# IMX8_eMMC.net
KiCad netlist of a schematic drawn in Altium Designer
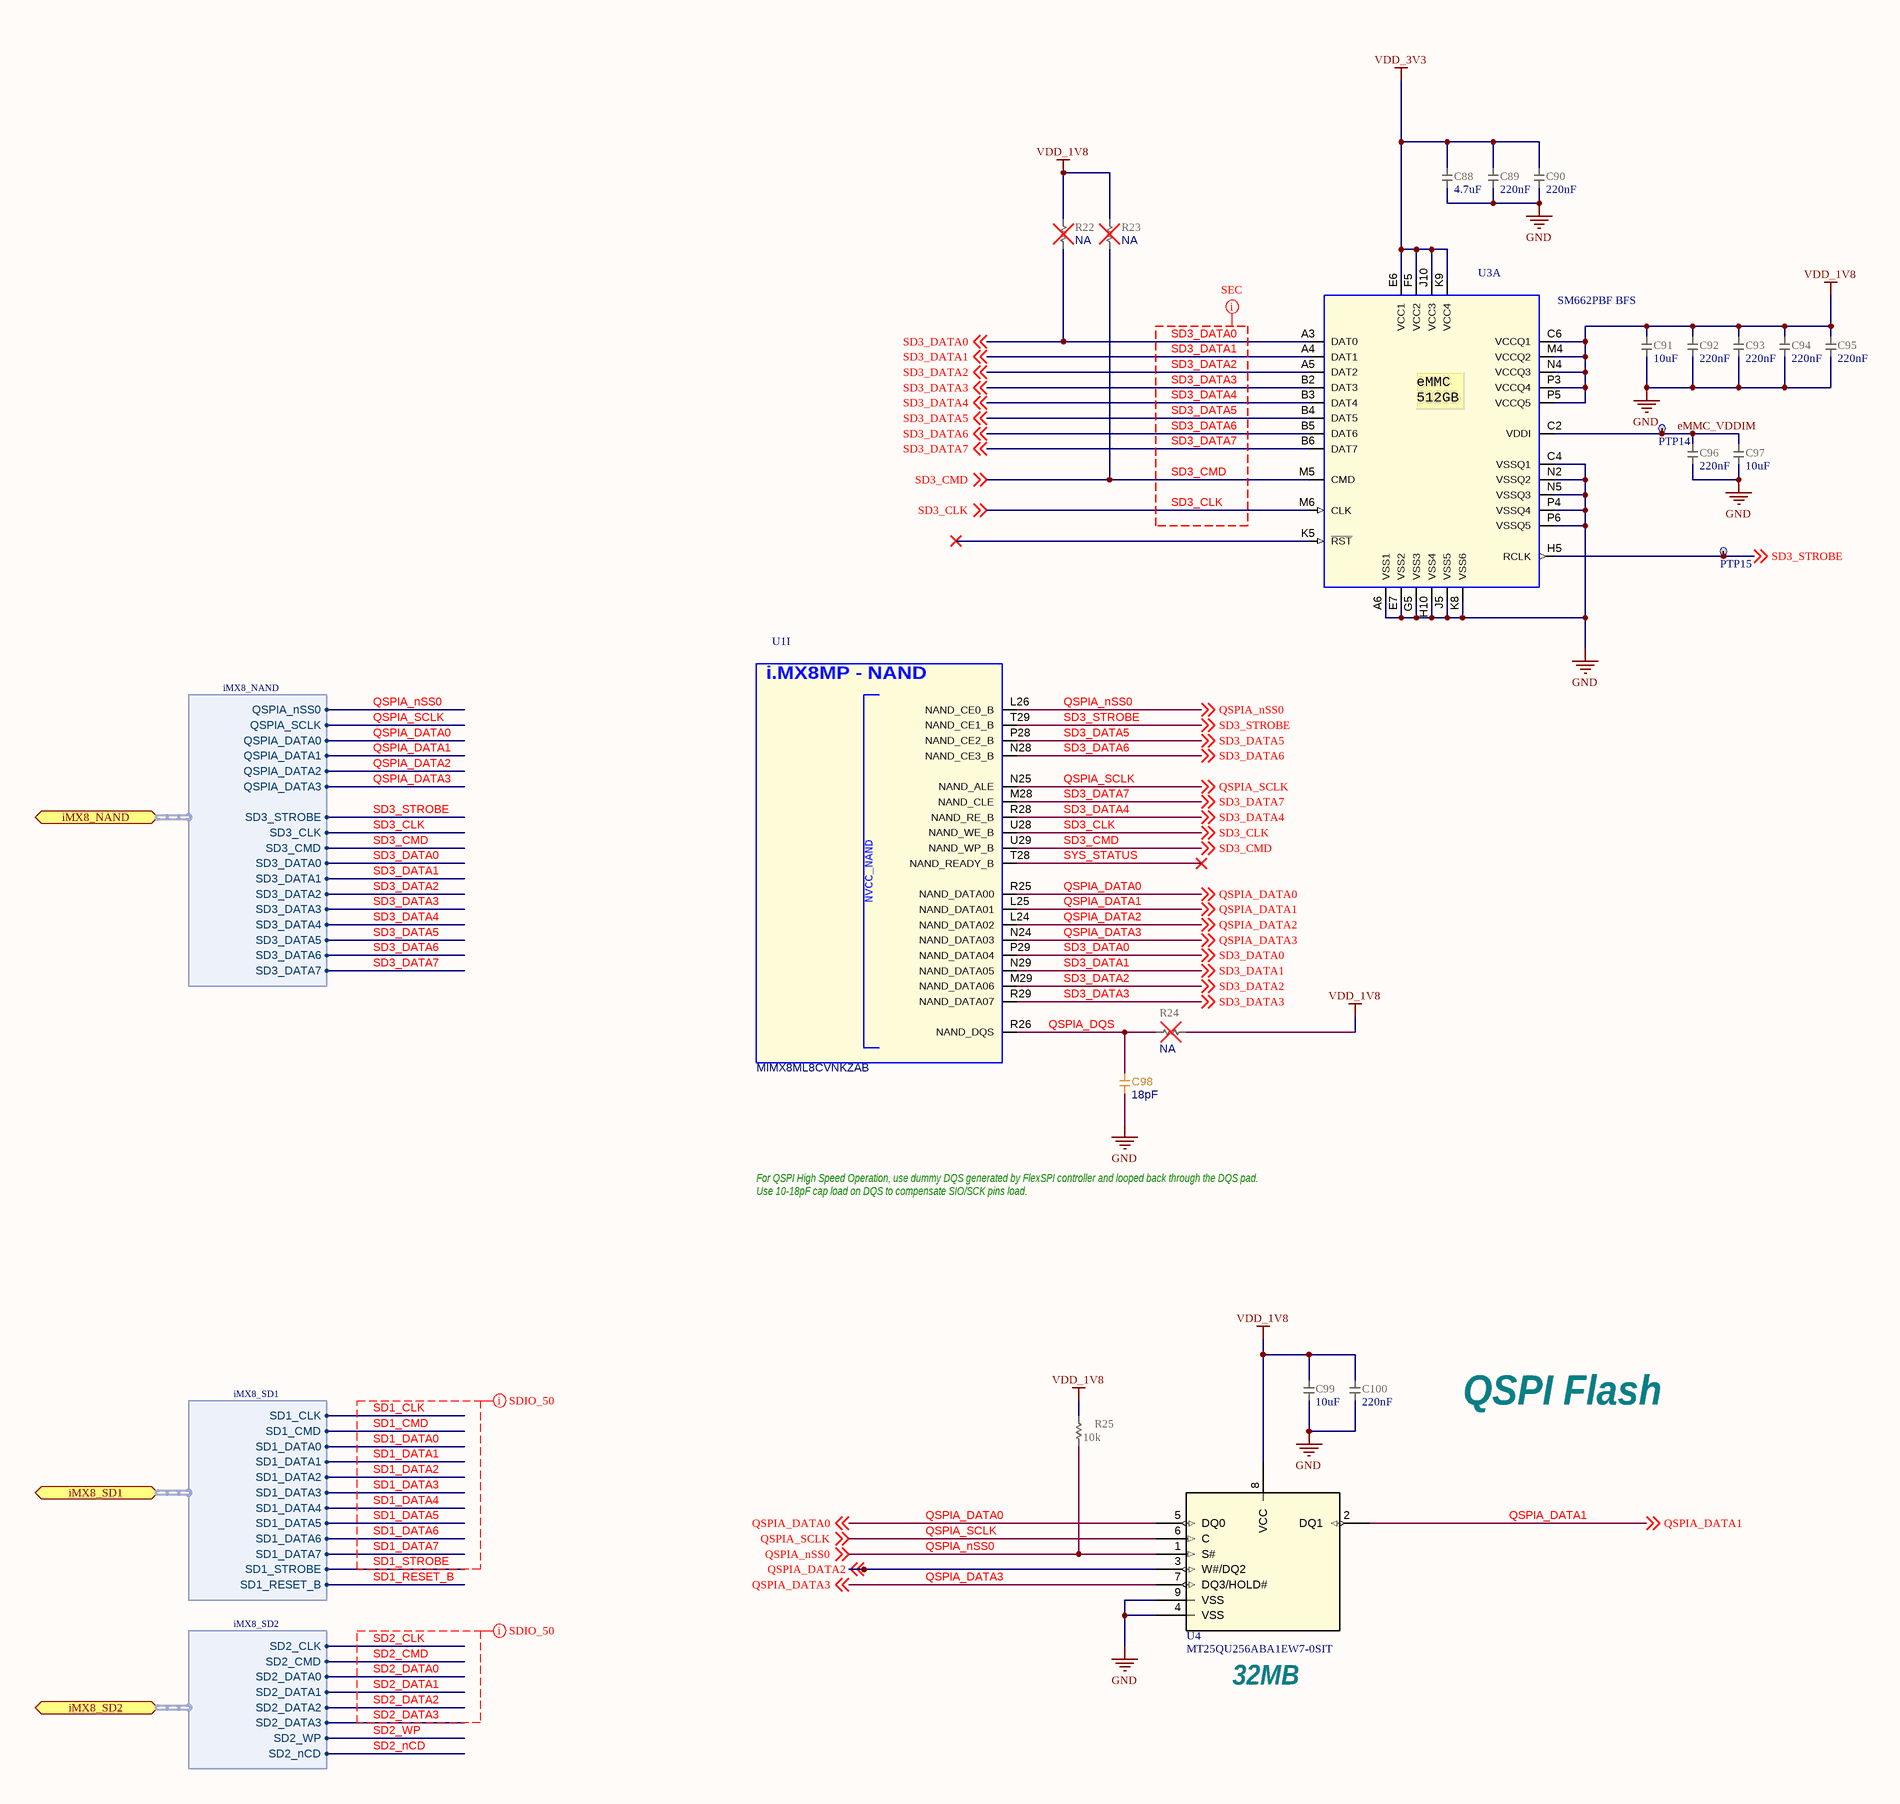
[diagram p0: IMX8_eMMC.SchDoc, left]
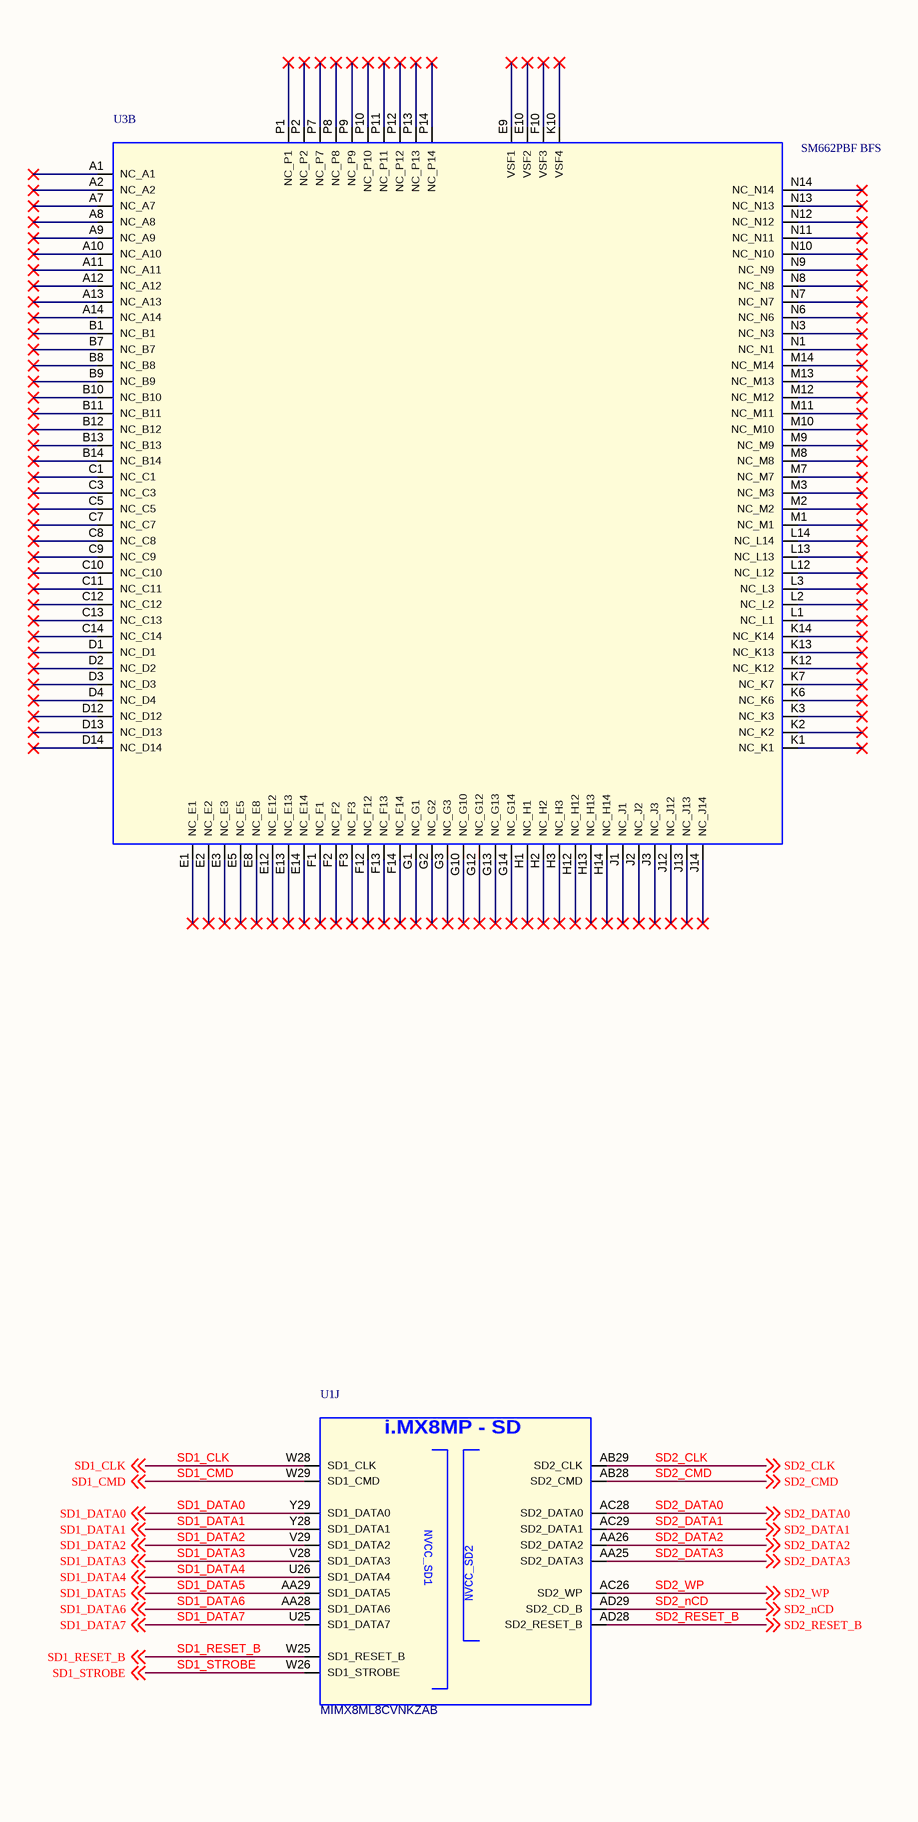
[diagram p1: IMX8_eMMC.SchDoc, right]

(export (version "E")
  (design (tool "Eeschema 10.0.6"))
  (components
    (comp (ref "C88")
      (value "4.7uF")
      (footprint "CAP_0402_H09W07_UN1Q")
      (description "CAP")
      (fields (field (name "PART NUMBER") "GRT155C81A475ME13J") (field (name "MANUFACTURER") "Murata"))
      (libsource (lib "robo_cam") (part "CMP-001-000888-12"))
    )
    (comp (ref "C89")
      (value "220nF")
      (footprint "CAP_0201_UN1Q")
      (description "CAP")
      (fields (field (name "PART NUMBER") "GRM033C81A224KE01D") (field (name "MANUFACTURER") "Murata"))
      (libsource (lib "robo_cam") (part "CMP-001-000889-11"))
    )
    (comp (ref "C90")
      (value "220nF")
      (footprint "CAP_0201_UN1Q")
      (description "CAP")
      (fields (field (name "PART NUMBER") "GRM033C81A224KE01D") (field (name "MANUFACTURER") "Murata"))
      (libsource (lib "robo_cam") (part "CMP-001-000889-11"))
    )
    (comp (ref "C91")
      (value "10uF")
      (footprint "CAP_0402_H09W07_UN1Q")
      (description "CAP")
      (fields (field (name "VOLTAGE") "6.3V") (field (name "TOLERANCE") "+/-20%"))
      (libsource (lib "robo_cam") (part "CMP-001-000883-14"))
    )
    (comp (ref "C92")
      (value "220nF")
      (footprint "CAP_0201_UN1Q")
      (description "CAP")
      (fields (field (name "PART NUMBER") "GRM033C81A224KE01D") (field (name "MANUFACTURER") "Murata"))
      (libsource (lib "robo_cam") (part "CMP-001-000889-11"))
    )
    (comp (ref "C93")
      (value "220nF")
      (footprint "CAP_0201_UN1Q")
      (description "CAP")
      (fields (field (name "PART NUMBER") "GRM033C81A224KE01D") (field (name "MANUFACTURER") "Murata"))
      (libsource (lib "robo_cam") (part "CMP-001-000889-11"))
    )
    (comp (ref "C94")
      (value "220nF")
      (footprint "CAP_0201_UN1Q")
      (description "CAP")
      (fields (field (name "PART NUMBER") "GRM033C81A224KE01D") (field (name "MANUFACTURER") "Murata"))
      (libsource (lib "robo_cam") (part "CMP-001-000889-11"))
    )
    (comp (ref "C95")
      (value "220nF")
      (footprint "CAP_0201_UN1Q")
      (description "CAP")
      (fields (field (name "PART NUMBER") "GRM033C81A224KE01D") (field (name "MANUFACTURER") "Murata"))
      (libsource (lib "robo_cam") (part "CMP-001-000889-11"))
    )
    (comp (ref "C96")
      (value "220nF")
      (footprint "CAP_0201_UN1Q")
      (description "CAP")
      (fields (field (name "PART NUMBER") "GRM033C81A224KE01D") (field (name "MANUFACTURER") "Murata"))
      (libsource (lib "robo_cam") (part "CMP-001-000889-11"))
    )
    (comp (ref "C97")
      (value "10uF")
      (footprint "CAP_0402_H09W07_UN1Q")
      (description "CAP")
      (fields (field (name "VOLTAGE") "6.3V") (field (name "TOLERANCE") "+/-20%"))
      (libsource (lib "robo_cam") (part "CMP-001-000883-14"))
    )
    (comp (ref "C98")
      (value "18pF")
      (footprint "CAP_0201_UN1Q")
      (description "CAP_RF_MATCHING")
      (fields (field (name "VOLTAGE") "25V") (field (name "TOLERANCE") "+/-2%"))
      (libsource (lib "robo_cam") (part "CMP-001-000400-12"))
    )
    (comp (ref "C99")
      (value "10uF")
      (footprint "CAP_0402_H09W07_UN1Q")
      (description "CAP")
      (fields (field (name "VOLTAGE") "6.3V") (field (name "TOLERANCE") "+/-20%"))
      (libsource (lib "robo_cam") (part "CMP-001-000883-14"))
    )
    (comp (ref "C100")
      (value "220nF")
      (footprint "CAP_0201_UN1Q")
      (description "CAP")
      (fields (field (name "PART NUMBER") "GRM033C81A224KE01D") (field (name "MANUFACTURER") "Murata"))
      (libsource (lib "robo_cam") (part "CMP-001-000889-11"))
    )
    (comp (ref "PTP14")
      (value "PTP_0.4mm")
      (footprint "PTP_0.4mm")
      (description "Production Testpoint 0.4mm. Flying probe. Use 1mm pitch.")
      (fields (field (name "PART NUMBER") "PTP 0.4mm"))
      (libsource (lib "robo_cam") (part "CMP-001-001296-3"))
    )
    (comp (ref "PTP15")
      (value "PTP_0.4mm")
      (footprint "PTP_0.4mm")
      (description "Production Testpoint 0.4mm. Flying probe. Use 1mm pitch.")
      (fields (field (name "PART NUMBER") "PTP 0.4mm"))
      (libsource (lib "robo_cam") (part "CMP-001-001296-3"))
    )
    (comp (ref "R22")
      (value "NA")
      (footprint "RES_0201_UN1Q")
      (description "Not Assembled - RES")
      (fields (field (name "Comment") "RES_0201_NA"))
      (libsource (lib "robo_cam") (part "CMP-001-000434-10"))
    )
    (comp (ref "R23")
      (value "NA")
      (footprint "RES_0201_UN1Q")
      (description "Not Assembled - RES")
      (fields (field (name "Comment") "RES_0201_NA"))
      (libsource (lib "robo_cam") (part "CMP-001-000434-10"))
    )
    (comp (ref "R24")
      (value "NA")
      (footprint "RES_0201_UN1Q")
      (description "Not Assembled - RES")
      (fields (field (name "Comment") "RES_0201_NA"))
      (libsource (lib "robo_cam") (part "CMP-001-000434-10"))
    )
    (comp (ref "R25")
      (value "10k")
      (footprint "RES_0201_UN1Q")
      (description "RES")
      (fields (field (name "TOLERANCE") "+/-1%"))
      (libsource (lib "RLC_UN1Q") (part "RES_0201_10k"))
    )
    (comp (ref "U1")
      (value "MIMX8ML8CVNKZAB")
      (footprint "BGA548C50P29X29_1500X1500X148")
      (description "CPU QUAD CORTEX A53+M4 1.6GHZ BGA548 Industrial")
      (fields
        (field (name "MANUFACTURER") "NXP Semiconductors")
        (field (name "PART NUMBER") "MIMX8ML8CVNKZAB")
        (field (name "SOURCE") "UUDET_KOMPONENTIT.SchLib")
      )
      (libsource (lib "robo_cam") (part "CMP-001-000983-8"))
    )
    (comp (ref "U3")
      (value "SM662PBF BFS")
      (footprint "GA153C50P14X14_1150X1300X120")
      (description "MEM NAND FLASH 512GB eMMC 5.1 HS400 2.7-3.6V, 1.8V VCCQ, TFBGA153 Ferri-eMMC Automotive")
      (fields
        (field (name "MANUFACTURER") "Silicon Motion")
        (field (name "PART NUMBER") "SM662PBF BFS")
        (field (name "MANUFACTURER PART NUMBER") "SM662PBFBFSS")
      )
      (libsource (lib "robo_cam") (part "CMP-001-001175-2"))
    )
    (comp (ref "U4")
      (value "MT25QU256ABA1EW7-0SIT")
      (footprint "W-PDFN-8MLP8_W7_MRN")
      (description "Description")
      (fields (field (name "COPYRIGHT") "Copyright (C) 2025 Ultra Librarian. All rights reserved."))
      (libsource (lib "MT25QU256ABA1EW7-0SIT") (part "MT25QU256ABA1EW7-0SIT"))
    )
  )
  (nets
    (net (code "4") (name "/QSPIA_DQS") (class "Default")
      (node (ref "C98") (pin "2") (pinfunction "2_2") (pintype "passive"))
      (node (ref "R24") (pin "1") (pinfunction "1_1") (pintype "passive"))
      (node (ref "U1") (pin "R26") (pinfunction "NAND_DQS_R26") (pintype "passive"))
    )
    (net (code "5") (name "/SYS_STATUS") (class "Default")
      (node (ref "U1") (pin "T28") (pinfunction "NAND_READY_B_T28") (pintype "passive+no_connect"))
    )
    (net (code "6") (name "/eMMC_VDDIM") (class "Default")
      (node (ref "C96") (pin "2") (pinfunction "2_2") (pintype "passive"))
      (node (ref "C97") (pin "1") (pinfunction "1_1") (pintype "passive"))
      (node (ref "PTP14") (pin "1") (pinfunction "TP_1") (pintype "passive"))
      (node (ref "U3") (pin "C2") (pinfunction "VDDI_C2") (pintype "power_in"))
    )
    (net (code "10") (name "GND") (class "Default")
      (node (ref "C100") (pin "2") (pinfunction "2_2") (pintype "passive"))
      (node (ref "C88") (pin "1") (pinfunction "1_1") (pintype "passive"))
      (node (ref "C89") (pin "1") (pinfunction "1_1") (pintype "passive"))
      (node (ref "C90") (pin "1") (pinfunction "1_1") (pintype "passive"))
      (node (ref "C91") (pin "2") (pinfunction "2_2") (pintype "passive"))
      (node (ref "C92") (pin "1") (pinfunction "1_1") (pintype "passive"))
      (node (ref "C93") (pin "1") (pinfunction "1_1") (pintype "passive"))
      (node (ref "C94") (pin "1") (pinfunction "1_1") (pintype "passive"))
      (node (ref "C95") (pin "1") (pinfunction "1_1") (pintype "passive"))
      (node (ref "C96") (pin "1") (pinfunction "1_1") (pintype "passive"))
      (node (ref "C97") (pin "2") (pinfunction "2_2") (pintype "passive"))
      (node (ref "C98") (pin "1") (pinfunction "1_1") (pintype "passive"))
      (node (ref "C99") (pin "2") (pinfunction "2_2") (pintype "passive"))
      (node (ref "U3") (pin "A6") (pinfunction "VSS1_A6") (pintype "power_in"))
      (node (ref "U3") (pin "C4") (pinfunction "VSSQ1_C4") (pintype "power_in"))
      (node (ref "U3") (pin "E7") (pinfunction "VSS2_E7") (pintype "power_in"))
      (node (ref "U3") (pin "G5") (pinfunction "VSS3_G5") (pintype "power_in"))
      (node (ref "U3") (pin "H10") (pinfunction "VSS4_H10") (pintype "power_in"))
      (node (ref "U3") (pin "J5") (pinfunction "VSS5_J5") (pintype "power_in"))
      (node (ref "U3") (pin "K8") (pinfunction "VSS6_K8") (pintype "power_in"))
      (node (ref "U3") (pin "N2") (pinfunction "VSSQ2_N2") (pintype "power_in"))
      (node (ref "U3") (pin "N5") (pinfunction "VSSQ3_N5") (pintype "power_in"))
      (node (ref "U3") (pin "P4") (pinfunction "VSSQ4_P4") (pintype "power_in"))
      (node (ref "U3") (pin "P6") (pinfunction "VSSQ5_P6") (pintype "power_in"))
      (node (ref "U4") (pin "4") (pinfunction "VSS_4") (pintype "power_in"))
      (node (ref "U4") (pin "9") (pinfunction "VSS_9") (pintype "power_in"))
    )
    (net (code "11") (name "QSPIA_DATA0") (class "Default")
      (node (ref "U1") (pin "R25") (pinfunction "NAND_DATA00_R25") (pintype "passive"))
      (node (ref "U4") (pin "5") (pinfunction "DQ0_5") (pintype "bidirectional"))
    )
    (net (code "12") (name "QSPIA_DATA1") (class "Default")
      (node (ref "U1") (pin "L25") (pinfunction "NAND_DATA01_L25") (pintype "passive"))
      (node (ref "U4") (pin "2") (pinfunction "DQ1_2") (pintype "bidirectional"))
    )
    (net (code "13") (name "QSPIA_DATA2") (class "Default")
      (node (ref "U1") (pin "L24") (pinfunction "NAND_DATA02_L24") (pintype "passive"))
      (node (ref "U4") (pin "3") (pinfunction "W#/DQ2_3") (pintype "bidirectional"))
    )
    (net (code "14") (name "QSPIA_DATA3") (class "Default")
      (node (ref "U1") (pin "N24") (pinfunction "NAND_DATA03_N24") (pintype "passive"))
      (node (ref "U4") (pin "7") (pinfunction "DQ3/HOLD#_7") (pintype "bidirectional"))
    )
    (net (code "15") (name "QSPIA_SCLK") (class "Default")
      (node (ref "U1") (pin "N25") (pinfunction "NAND_ALE_N25") (pintype "passive"))
      (node (ref "U4") (pin "6") (pinfunction "C_6") (pintype "input"))
    )
    (net (code "16") (name "QSPIA_nSS0") (class "Default")
      (node (ref "R25") (pin "1") (pinfunction "1_1") (pintype "passive"))
      (node (ref "U1") (pin "L26") (pinfunction "NAND_CE0_B_L26") (pintype "passive"))
      (node (ref "U4") (pin "1") (pinfunction "S#_1") (pintype "input"))
    )
    (net (code "17") (name "SD1_CLK") (class "Default")
      (node (ref "U1") (pin "W28") (pinfunction "SD1_CLK_W28") (pintype "passive"))
    )
    (net (code "18") (name "SD1_CMD") (class "Default")
      (node (ref "U1") (pin "W29") (pinfunction "SD1_CMD_W29") (pintype "passive"))
    )
    (net (code "19") (name "SD1_DATA0") (class "Default")
      (node (ref "U1") (pin "Y29") (pinfunction "SD1_DATA0_Y29") (pintype "passive"))
    )
    (net (code "20") (name "SD1_DATA1") (class "Default")
      (node (ref "U1") (pin "Y28") (pinfunction "SD1_DATA1_Y28") (pintype "passive"))
    )
    (net (code "21") (name "SD1_DATA2") (class "Default")
      (node (ref "U1") (pin "V29") (pinfunction "SD1_DATA2_V29") (pintype "passive"))
    )
    (net (code "22") (name "SD1_DATA3") (class "Default")
      (node (ref "U1") (pin "V28") (pinfunction "SD1_DATA3_V28") (pintype "passive"))
    )
    (net (code "23") (name "SD1_DATA4") (class "Default")
      (node (ref "U1") (pin "U26") (pinfunction "SD1_DATA4_U26") (pintype "passive"))
    )
    (net (code "24") (name "SD1_DATA5") (class "Default")
      (node (ref "U1") (pin "AA29") (pinfunction "SD1_DATA5_AA29") (pintype "passive"))
    )
    (net (code "25") (name "SD1_DATA6") (class "Default")
      (node (ref "U1") (pin "AA28") (pinfunction "SD1_DATA6_AA28") (pintype "passive"))
    )
    (net (code "26") (name "SD1_DATA7") (class "Default")
      (node (ref "U1") (pin "U25") (pinfunction "SD1_DATA7_U25") (pintype "passive"))
    )
    (net (code "27") (name "SD1_RESET_B") (class "Default")
      (node (ref "U1") (pin "W25") (pinfunction "SD1_RESET_B_W25") (pintype "passive"))
    )
    (net (code "28") (name "SD1_STROBE") (class "Default")
      (node (ref "U1") (pin "W26") (pinfunction "SD1_STROBE_W26") (pintype "passive"))
    )
    (net (code "29") (name "SD2_CLK") (class "Default")
      (node (ref "U1") (pin "AB29") (pinfunction "SD2_CLK_AB29") (pintype "passive"))
    )
    (net (code "30") (name "SD2_CMD") (class "Default")
      (node (ref "U1") (pin "AB28") (pinfunction "SD2_CMD_AB28") (pintype "passive"))
    )
    (net (code "31") (name "SD2_DATA0") (class "Default")
      (node (ref "U1") (pin "AC28") (pinfunction "SD2_DATA0_AC28") (pintype "passive"))
    )
    (net (code "32") (name "SD2_DATA1") (class "Default")
      (node (ref "U1") (pin "AC29") (pinfunction "SD2_DATA1_AC29") (pintype "passive"))
    )
    (net (code "33") (name "SD2_DATA2") (class "Default")
      (node (ref "U1") (pin "AA26") (pinfunction "SD2_DATA2_AA26") (pintype "passive"))
    )
    (net (code "34") (name "SD2_DATA3") (class "Default")
      (node (ref "U1") (pin "AA25") (pinfunction "SD2_DATA3_AA25") (pintype "passive"))
    )
    (net (code "35") (name "SD2_RESET_B") (class "Default")
      (node (ref "U1") (pin "AD28") (pinfunction "SD2_RESET_B_AD28") (pintype "passive"))
    )
    (net (code "36") (name "SD2_WP") (class "Default")
      (node (ref "U1") (pin "AC26") (pinfunction "SD2_WP_AC26") (pintype "passive"))
    )
    (net (code "37") (name "SD2_nCD") (class "Default")
      (node (ref "U1") (pin "AD29") (pinfunction "SD2_CD_B_AD29") (pintype "passive"))
    )
    (net (code "38") (name "SD3_CLK") (class "Default")
      (node (ref "U1") (pin "U28") (pinfunction "NAND_WE_B_U28") (pintype "passive"))
      (node (ref "U3") (pin "M6") (pinfunction "CLK_M6") (pintype "input"))
    )
    (net (code "39") (name "SD3_CMD") (class "Default")
      (node (ref "R23") (pin "1") (pinfunction "1_1") (pintype "passive"))
      (node (ref "U1") (pin "U29") (pinfunction "NAND_WP_B_U29") (pintype "passive"))
      (node (ref "U3") (pin "M5") (pinfunction "CMD_M5") (pintype "bidirectional"))
    )
    (net (code "40") (name "SD3_DATA0") (class "Default")
      (node (ref "R22") (pin "1") (pinfunction "1_1") (pintype "passive"))
      (node (ref "U1") (pin "P29") (pinfunction "NAND_DATA04_P29") (pintype "passive"))
      (node (ref "U3") (pin "A3") (pinfunction "DAT0_A3") (pintype "bidirectional"))
    )
    (net (code "41") (name "SD3_DATA1") (class "Default")
      (node (ref "U1") (pin "N29") (pinfunction "NAND_DATA05_N29") (pintype "passive"))
      (node (ref "U3") (pin "A4") (pinfunction "DAT1_A4") (pintype "bidirectional"))
    )
    (net (code "42") (name "SD3_DATA2") (class "Default")
      (node (ref "U1") (pin "M29") (pinfunction "NAND_DATA06_M29") (pintype "passive"))
      (node (ref "U3") (pin "A5") (pinfunction "DAT2_A5") (pintype "bidirectional"))
    )
    (net (code "43") (name "SD3_DATA3") (class "Default")
      (node (ref "U1") (pin "R29") (pinfunction "NAND_DATA07_R29") (pintype "passive"))
      (node (ref "U3") (pin "B2") (pinfunction "DAT3_B2") (pintype "bidirectional"))
    )
    (net (code "44") (name "SD3_DATA4") (class "Default")
      (node (ref "U1") (pin "R28") (pinfunction "NAND_RE_B_R28") (pintype "passive"))
      (node (ref "U3") (pin "B3") (pinfunction "DAT4_B3") (pintype "bidirectional"))
    )
    (net (code "45") (name "SD3_DATA5") (class "Default")
      (node (ref "U1") (pin "P28") (pinfunction "NAND_CE2_B_P28") (pintype "passive"))
      (node (ref "U3") (pin "B4") (pinfunction "DAT5_B4") (pintype "bidirectional"))
    )
    (net (code "46") (name "SD3_DATA6") (class "Default")
      (node (ref "U1") (pin "N28") (pinfunction "NAND_CE3_B_N28") (pintype "passive"))
      (node (ref "U3") (pin "B5") (pinfunction "DAT6_B5") (pintype "bidirectional"))
    )
    (net (code "47") (name "SD3_DATA7") (class "Default")
      (node (ref "U1") (pin "M28") (pinfunction "NAND_CLE_M28") (pintype "passive"))
      (node (ref "U3") (pin "B6") (pinfunction "DAT7_B6") (pintype "bidirectional"))
    )
    (net (code "48") (name "SD3_STROBE") (class "Default")
      (node (ref "PTP15") (pin "1") (pinfunction "TP_1") (pintype "passive"))
      (node (ref "U1") (pin "T29") (pinfunction "NAND_CE1_B_T29") (pintype "passive"))
      (node (ref "U3") (pin "H5") (pinfunction "RCLK_H5") (pintype "output"))
    )
    (net (code "49") (name "VDD_1V8") (class "Default")
      (node (ref "C100") (pin "1") (pinfunction "1_1") (pintype "passive"))
      (node (ref "C91") (pin "1") (pinfunction "1_1") (pintype "passive"))
      (node (ref "C92") (pin "2") (pinfunction "2_2") (pintype "passive"))
      (node (ref "C93") (pin "2") (pinfunction "2_2") (pintype "passive"))
      (node (ref "C94") (pin "2") (pinfunction "2_2") (pintype "passive"))
      (node (ref "C95") (pin "2") (pinfunction "2_2") (pintype "passive"))
      (node (ref "C99") (pin "1") (pinfunction "1_1") (pintype "passive"))
      (node (ref "R22") (pin "2") (pinfunction "2_2") (pintype "passive"))
      (node (ref "R23") (pin "2") (pinfunction "2_2") (pintype "passive"))
      (node (ref "R24") (pin "2") (pinfunction "2_2") (pintype "passive"))
      (node (ref "R25") (pin "2") (pinfunction "2_2") (pintype "passive"))
      (node (ref "U3") (pin "C6") (pinfunction "VCCQ1_C6") (pintype "power_in"))
      (node (ref "U3") (pin "M4") (pinfunction "VCCQ2_M4") (pintype "power_in"))
      (node (ref "U3") (pin "N4") (pinfunction "VCCQ3_N4") (pintype "power_in"))
      (node (ref "U3") (pin "P3") (pinfunction "VCCQ4_P3") (pintype "power_in"))
      (node (ref "U3") (pin "P5") (pinfunction "VCCQ5_P5") (pintype "power_in"))
      (node (ref "U4") (pin "8") (pinfunction "VCC_8") (pintype "power_in"))
    )
    (net (code "50") (name "VDD_3V3") (class "Default")
      (node (ref "C88") (pin "2") (pinfunction "2_2") (pintype "passive"))
      (node (ref "C89") (pin "2") (pinfunction "2_2") (pintype "passive"))
      (node (ref "C90") (pin "2") (pinfunction "2_2") (pintype "passive"))
      (node (ref "U3") (pin "E6") (pinfunction "VCC1_E6") (pintype "power_in"))
      (node (ref "U3") (pin "F5") (pinfunction "VCC2_F5") (pintype "power_in"))
      (node (ref "U3") (pin "J10") (pinfunction "VCC3_J10") (pintype "power_in"))
      (node (ref "U3") (pin "K9") (pinfunction "VCC4_K9") (pintype "power_in"))
    )
    (net (code "51") (name "unconnected-(U3A-~{RST}-PadK5)") (class "Default")
      (node (ref "U3") (pin "K5") (pinfunction "~{RST}_K5") (pintype "input+no_connect"))
    )
    (net (code "52") (name "unconnected-(U3B-NC_A1-PadA1)") (class "Default")
      (node (ref "U3") (pin "A1") (pinfunction "NC_A1_A1") (pintype "passive+no_connect"))
    )
    (net (code "53") (name "unconnected-(U3B-NC_A2-PadA2)") (class "Default")
      (node (ref "U3") (pin "A2") (pinfunction "NC_A2_A2") (pintype "passive+no_connect"))
    )
    (net (code "54") (name "unconnected-(U3B-NC_A7-PadA7)") (class "Default")
      (node (ref "U3") (pin "A7") (pinfunction "NC_A7_A7") (pintype "passive+no_connect"))
    )
    (net (code "55") (name "unconnected-(U3B-NC_A8-PadA8)") (class "Default")
      (node (ref "U3") (pin "A8") (pinfunction "NC_A8_A8") (pintype "passive+no_connect"))
    )
    (net (code "56") (name "unconnected-(U3B-NC_A9-PadA9)") (class "Default")
      (node (ref "U3") (pin "A9") (pinfunction "NC_A9_A9") (pintype "passive+no_connect"))
    )
    (net (code "57") (name "unconnected-(U3B-NC_A10-PadA10)") (class "Default")
      (node (ref "U3") (pin "A10") (pinfunction "NC_A10_A10") (pintype "passive+no_connect"))
    )
    (net (code "58") (name "unconnected-(U3B-NC_A11-PadA11)") (class "Default")
      (node (ref "U3") (pin "A11") (pinfunction "NC_A11_A11") (pintype "passive+no_connect"))
    )
    (net (code "59") (name "unconnected-(U3B-NC_A12-PadA12)") (class "Default")
      (node (ref "U3") (pin "A12") (pinfunction "NC_A12_A12") (pintype "passive+no_connect"))
    )
    (net (code "60") (name "unconnected-(U3B-NC_A13-PadA13)") (class "Default")
      (node (ref "U3") (pin "A13") (pinfunction "NC_A13_A13") (pintype "passive+no_connect"))
    )
    (net (code "61") (name "unconnected-(U3B-NC_A14-PadA14)") (class "Default")
      (node (ref "U3") (pin "A14") (pinfunction "NC_A14_A14") (pintype "passive+no_connect"))
    )
    (net (code "62") (name "unconnected-(U3B-NC_B1-PadB1)") (class "Default")
      (node (ref "U3") (pin "B1") (pinfunction "NC_B1_B1") (pintype "passive+no_connect"))
    )
    (net (code "63") (name "unconnected-(U3B-NC_B7-PadB7)") (class "Default")
      (node (ref "U3") (pin "B7") (pinfunction "NC_B7_B7") (pintype "passive+no_connect"))
    )
    (net (code "64") (name "unconnected-(U3B-NC_B8-PadB8)") (class "Default")
      (node (ref "U3") (pin "B8") (pinfunction "NC_B8_B8") (pintype "passive+no_connect"))
    )
    (net (code "65") (name "unconnected-(U3B-NC_B9-PadB9)") (class "Default")
      (node (ref "U3") (pin "B9") (pinfunction "NC_B9_B9") (pintype "passive+no_connect"))
    )
    (net (code "66") (name "unconnected-(U3B-NC_B10-PadB10)") (class "Default")
      (node (ref "U3") (pin "B10") (pinfunction "NC_B10_B10") (pintype "passive+no_connect"))
    )
    (net (code "67") (name "unconnected-(U3B-NC_B11-PadB11)") (class "Default")
      (node (ref "U3") (pin "B11") (pinfunction "NC_B11_B11") (pintype "passive+no_connect"))
    )
    (net (code "68") (name "unconnected-(U3B-NC_B12-PadB12)") (class "Default")
      (node (ref "U3") (pin "B12") (pinfunction "NC_B12_B12") (pintype "passive+no_connect"))
    )
    (net (code "69") (name "unconnected-(U3B-NC_B13-PadB13)") (class "Default")
      (node (ref "U3") (pin "B13") (pinfunction "NC_B13_B13") (pintype "passive+no_connect"))
    )
    (net (code "70") (name "unconnected-(U3B-NC_B14-PadB14)") (class "Default")
      (node (ref "U3") (pin "B14") (pinfunction "NC_B14_B14") (pintype "passive+no_connect"))
    )
    (net (code "71") (name "unconnected-(U3B-NC_C1-PadC1)") (class "Default")
      (node (ref "U3") (pin "C1") (pinfunction "NC_C1_C1") (pintype "passive+no_connect"))
    )
    (net (code "72") (name "unconnected-(U3B-NC_C3-PadC3)") (class "Default")
      (node (ref "U3") (pin "C3") (pinfunction "NC_C3_C3") (pintype "passive+no_connect"))
    )
    (net (code "73") (name "unconnected-(U3B-NC_C5-PadC5)") (class "Default")
      (node (ref "U3") (pin "C5") (pinfunction "NC_C5_C5") (pintype "passive+no_connect"))
    )
    (net (code "74") (name "unconnected-(U3B-NC_C7-PadC7)") (class "Default")
      (node (ref "U3") (pin "C7") (pinfunction "NC_C7_C7") (pintype "passive+no_connect"))
    )
    (net (code "75") (name "unconnected-(U3B-NC_C8-PadC8)") (class "Default")
      (node (ref "U3") (pin "C8") (pinfunction "NC_C8_C8") (pintype "passive+no_connect"))
    )
    (net (code "76") (name "unconnected-(U3B-NC_C9-PadC9)") (class "Default")
      (node (ref "U3") (pin "C9") (pinfunction "NC_C9_C9") (pintype "passive+no_connect"))
    )
    (net (code "77") (name "unconnected-(U3B-NC_C10-PadC10)") (class "Default")
      (node (ref "U3") (pin "C10") (pinfunction "NC_C10_C10") (pintype "passive+no_connect"))
    )
    (net (code "78") (name "unconnected-(U3B-NC_C11-PadC11)") (class "Default")
      (node (ref "U3") (pin "C11") (pinfunction "NC_C11_C11") (pintype "passive+no_connect"))
    )
    (net (code "79") (name "unconnected-(U3B-NC_C12-PadC12)") (class "Default")
      (node (ref "U3") (pin "C12") (pinfunction "NC_C12_C12") (pintype "passive+no_connect"))
    )
    (net (code "80") (name "unconnected-(U3B-NC_C13-PadC13)") (class "Default")
      (node (ref "U3") (pin "C13") (pinfunction "NC_C13_C13") (pintype "passive+no_connect"))
    )
    (net (code "81") (name "unconnected-(U3B-NC_C14-PadC14)") (class "Default")
      (node (ref "U3") (pin "C14") (pinfunction "NC_C14_C14") (pintype "passive+no_connect"))
    )
    (net (code "82") (name "unconnected-(U3B-NC_D1-PadD1)") (class "Default")
      (node (ref "U3") (pin "D1") (pinfunction "NC_D1_D1") (pintype "passive+no_connect"))
    )
    (net (code "83") (name "unconnected-(U3B-NC_D2-PadD2)") (class "Default")
      (node (ref "U3") (pin "D2") (pinfunction "NC_D2_D2") (pintype "passive+no_connect"))
    )
    (net (code "84") (name "unconnected-(U3B-NC_D3-PadD3)") (class "Default")
      (node (ref "U3") (pin "D3") (pinfunction "NC_D3_D3") (pintype "passive+no_connect"))
    )
    (net (code "85") (name "unconnected-(U3B-NC_D4-PadD4)") (class "Default")
      (node (ref "U3") (pin "D4") (pinfunction "NC_D4_D4") (pintype "passive+no_connect"))
    )
    (net (code "86") (name "unconnected-(U3B-NC_D12-PadD12)") (class "Default")
      (node (ref "U3") (pin "D12") (pinfunction "NC_D12_D12") (pintype "passive+no_connect"))
    )
    (net (code "87") (name "unconnected-(U3B-NC_D13-PadD13)") (class "Default")
      (node (ref "U3") (pin "D13") (pinfunction "NC_D13_D13") (pintype "passive+no_connect"))
    )
    (net (code "88") (name "unconnected-(U3B-NC_D14-PadD14)") (class "Default")
      (node (ref "U3") (pin "D14") (pinfunction "NC_D14_D14") (pintype "passive+no_connect"))
    )
    (net (code "89") (name "unconnected-(U3B-NC_E1-PadE1)") (class "Default")
      (node (ref "U3") (pin "E1") (pinfunction "NC_E1_E1") (pintype "passive+no_connect"))
    )
    (net (code "90") (name "unconnected-(U3B-NC_E2-PadE2)") (class "Default")
      (node (ref "U3") (pin "E2") (pinfunction "NC_E2_E2") (pintype "passive+no_connect"))
    )
    (net (code "91") (name "unconnected-(U3B-NC_E3-PadE3)") (class "Default")
      (node (ref "U3") (pin "E3") (pinfunction "NC_E3_E3") (pintype "passive+no_connect"))
    )
    (net (code "92") (name "unconnected-(U3B-NC_E5-PadE5)") (class "Default")
      (node (ref "U3") (pin "E5") (pinfunction "NC_E5_E5") (pintype "passive+no_connect"))
    )
    (net (code "93") (name "unconnected-(U3B-NC_E8-PadE8)") (class "Default")
      (node (ref "U3") (pin "E8") (pinfunction "NC_E8_E8") (pintype "passive+no_connect"))
    )
    (net (code "94") (name "unconnected-(U3B-NC_E12-PadE12)") (class "Default")
      (node (ref "U3") (pin "E12") (pinfunction "NC_E12_E12") (pintype "passive+no_connect"))
    )
    (net (code "95") (name "unconnected-(U3B-NC_E13-PadE13)") (class "Default")
      (node (ref "U3") (pin "E13") (pinfunction "NC_E13_E13") (pintype "passive+no_connect"))
    )
    (net (code "96") (name "unconnected-(U3B-NC_E14-PadE14)") (class "Default")
      (node (ref "U3") (pin "E14") (pinfunction "NC_E14_E14") (pintype "passive+no_connect"))
    )
    (net (code "97") (name "unconnected-(U3B-NC_F1-PadF1)") (class "Default")
      (node (ref "U3") (pin "F1") (pinfunction "NC_F1_F1") (pintype "passive+no_connect"))
    )
    (net (code "98") (name "unconnected-(U3B-NC_F2-PadF2)") (class "Default")
      (node (ref "U3") (pin "F2") (pinfunction "NC_F2_F2") (pintype "passive+no_connect"))
    )
    (net (code "99") (name "unconnected-(U3B-NC_F3-PadF3)") (class "Default")
      (node (ref "U3") (pin "F3") (pinfunction "NC_F3_F3") (pintype "passive+no_connect"))
    )
    (net (code "100") (name "unconnected-(U3B-NC_F12-PadF12)") (class "Default")
      (node (ref "U3") (pin "F12") (pinfunction "NC_F12_F12") (pintype "passive+no_connect"))
    )
    (net (code "101") (name "unconnected-(U3B-NC_F13-PadF13)") (class "Default")
      (node (ref "U3") (pin "F13") (pinfunction "NC_F13_F13") (pintype "passive+no_connect"))
    )
    (net (code "102") (name "unconnected-(U3B-NC_F14-PadF14)") (class "Default")
      (node (ref "U3") (pin "F14") (pinfunction "NC_F14_F14") (pintype "passive+no_connect"))
    )
    (net (code "103") (name "unconnected-(U3B-NC_G1-PadG1)") (class "Default")
      (node (ref "U3") (pin "G1") (pinfunction "NC_G1_G1") (pintype "passive+no_connect"))
    )
    (net (code "104") (name "unconnected-(U3B-NC_G2-PadG2)") (class "Default")
      (node (ref "U3") (pin "G2") (pinfunction "NC_G2_G2") (pintype "passive+no_connect"))
    )
    (net (code "105") (name "unconnected-(U3B-NC_G3-PadG3)") (class "Default")
      (node (ref "U3") (pin "G3") (pinfunction "NC_G3_G3") (pintype "passive+no_connect"))
    )
    (net (code "106") (name "unconnected-(U3B-NC_G10-PadG10)") (class "Default")
      (node (ref "U3") (pin "G10") (pinfunction "NC_G10_G10") (pintype "passive+no_connect"))
    )
    (net (code "107") (name "unconnected-(U3B-NC_G12-PadG12)") (class "Default")
      (node (ref "U3") (pin "G12") (pinfunction "NC_G12_G12") (pintype "passive+no_connect"))
    )
    (net (code "108") (name "unconnected-(U3B-NC_G13-PadG13)") (class "Default")
      (node (ref "U3") (pin "G13") (pinfunction "NC_G13_G13") (pintype "passive+no_connect"))
    )
    (net (code "109") (name "unconnected-(U3B-NC_G14-PadG14)") (class "Default")
      (node (ref "U3") (pin "G14") (pinfunction "NC_G14_G14") (pintype "passive+no_connect"))
    )
    (net (code "110") (name "unconnected-(U3B-NC_H1-PadH1)") (class "Default")
      (node (ref "U3") (pin "H1") (pinfunction "NC_H1_H1") (pintype "passive+no_connect"))
    )
    (net (code "111") (name "unconnected-(U3B-NC_H2-PadH2)") (class "Default")
      (node (ref "U3") (pin "H2") (pinfunction "NC_H2_H2") (pintype "passive+no_connect"))
    )
    (net (code "112") (name "unconnected-(U3B-NC_H3-PadH3)") (class "Default")
      (node (ref "U3") (pin "H3") (pinfunction "NC_H3_H3") (pintype "passive+no_connect"))
    )
    (net (code "113") (name "unconnected-(U3B-NC_H12-PadH12)") (class "Default")
      (node (ref "U3") (pin "H12") (pinfunction "NC_H12_H12") (pintype "passive+no_connect"))
    )
    (net (code "114") (name "unconnected-(U3B-NC_H13-PadH13)") (class "Default")
      (node (ref "U3") (pin "H13") (pinfunction "NC_H13_H13") (pintype "passive+no_connect"))
    )
    (net (code "115") (name "unconnected-(U3B-NC_H14-PadH14)") (class "Default")
      (node (ref "U3") (pin "H14") (pinfunction "NC_H14_H14") (pintype "passive+no_connect"))
    )
    (net (code "116") (name "unconnected-(U3B-NC_J1-PadJ1)") (class "Default")
      (node (ref "U3") (pin "J1") (pinfunction "NC_J1_J1") (pintype "passive+no_connect"))
    )
    (net (code "117") (name "unconnected-(U3B-NC_J2-PadJ2)") (class "Default")
      (node (ref "U3") (pin "J2") (pinfunction "NC_J2_J2") (pintype "passive+no_connect"))
    )
    (net (code "118") (name "unconnected-(U3B-NC_J3-PadJ3)") (class "Default")
      (node (ref "U3") (pin "J3") (pinfunction "NC_J3_J3") (pintype "passive+no_connect"))
    )
    (net (code "119") (name "unconnected-(U3B-NC_J12-PadJ12)") (class "Default")
      (node (ref "U3") (pin "J12") (pinfunction "NC_J12_J12") (pintype "passive+no_connect"))
    )
    (net (code "120") (name "unconnected-(U3B-NC_J13-PadJ13)") (class "Default")
      (node (ref "U3") (pin "J13") (pinfunction "NC_J13_J13") (pintype "passive+no_connect"))
    )
    (net (code "121") (name "unconnected-(U3B-NC_J14-PadJ14)") (class "Default")
      (node (ref "U3") (pin "J14") (pinfunction "NC_J14_J14") (pintype "passive+no_connect"))
    )
    (net (code "122") (name "unconnected-(U3B-NC_K1-PadK1)") (class "Default")
      (node (ref "U3") (pin "K1") (pinfunction "NC_K1_K1") (pintype "passive+no_connect"))
    )
    (net (code "123") (name "unconnected-(U3B-NC_K2-PadK2)") (class "Default")
      (node (ref "U3") (pin "K2") (pinfunction "NC_K2_K2") (pintype "passive+no_connect"))
    )
    (net (code "124") (name "unconnected-(U3B-NC_K3-PadK3)") (class "Default")
      (node (ref "U3") (pin "K3") (pinfunction "NC_K3_K3") (pintype "passive+no_connect"))
    )
    (net (code "125") (name "unconnected-(U3B-NC_K6-PadK6)") (class "Default")
      (node (ref "U3") (pin "K6") (pinfunction "NC_K6_K6") (pintype "passive+no_connect"))
    )
    (net (code "126") (name "unconnected-(U3B-NC_K7-PadK7)") (class "Default")
      (node (ref "U3") (pin "K7") (pinfunction "NC_K7_K7") (pintype "passive+no_connect"))
    )
    (net (code "127") (name "unconnected-(U3B-NC_K12-PadK12)") (class "Default")
      (node (ref "U3") (pin "K12") (pinfunction "NC_K12_K12") (pintype "passive+no_connect"))
    )
    (net (code "128") (name "unconnected-(U3B-NC_K13-PadK13)") (class "Default")
      (node (ref "U3") (pin "K13") (pinfunction "NC_K13_K13") (pintype "passive+no_connect"))
    )
    (net (code "129") (name "unconnected-(U3B-NC_K14-PadK14)") (class "Default")
      (node (ref "U3") (pin "K14") (pinfunction "NC_K14_K14") (pintype "passive+no_connect"))
    )
    (net (code "130") (name "unconnected-(U3B-NC_L1-PadL1)") (class "Default")
      (node (ref "U3") (pin "L1") (pinfunction "NC_L1_L1") (pintype "passive+no_connect"))
    )
    (net (code "131") (name "unconnected-(U3B-NC_L2-PadL2)") (class "Default")
      (node (ref "U3") (pin "L2") (pinfunction "NC_L2_L2") (pintype "passive+no_connect"))
    )
    (net (code "132") (name "unconnected-(U3B-NC_L3-PadL3)") (class "Default")
      (node (ref "U3") (pin "L3") (pinfunction "NC_L3_L3") (pintype "passive+no_connect"))
    )
    (net (code "133") (name "unconnected-(U3B-NC_L12-PadL12)") (class "Default")
      (node (ref "U3") (pin "L12") (pinfunction "NC_L12_L12") (pintype "passive+no_connect"))
    )
    (net (code "134") (name "unconnected-(U3B-NC_L13-PadL13)") (class "Default")
      (node (ref "U3") (pin "L13") (pinfunction "NC_L13_L13") (pintype "passive+no_connect"))
    )
    (net (code "135") (name "unconnected-(U3B-NC_L14-PadL14)") (class "Default")
      (node (ref "U3") (pin "L14") (pinfunction "NC_L14_L14") (pintype "passive+no_connect"))
    )
    (net (code "136") (name "unconnected-(U3B-NC_M1-PadM1)") (class "Default")
      (node (ref "U3") (pin "M1") (pinfunction "NC_M1_M1") (pintype "passive+no_connect"))
    )
    (net (code "137") (name "unconnected-(U3B-NC_M2-PadM2)") (class "Default")
      (node (ref "U3") (pin "M2") (pinfunction "NC_M2_M2") (pintype "passive+no_connect"))
    )
    (net (code "138") (name "unconnected-(U3B-NC_M3-PadM3)") (class "Default")
      (node (ref "U3") (pin "M3") (pinfunction "NC_M3_M3") (pintype "passive+no_connect"))
    )
    (net (code "139") (name "unconnected-(U3B-NC_M7-PadM7)") (class "Default")
      (node (ref "U3") (pin "M7") (pinfunction "NC_M7_M7") (pintype "passive+no_connect"))
    )
    (net (code "140") (name "unconnected-(U3B-NC_M8-PadM8)") (class "Default")
      (node (ref "U3") (pin "M8") (pinfunction "NC_M8_M8") (pintype "passive+no_connect"))
    )
    (net (code "141") (name "unconnected-(U3B-NC_M9-PadM9)") (class "Default")
      (node (ref "U3") (pin "M9") (pinfunction "NC_M9_M9") (pintype "passive+no_connect"))
    )
    (net (code "142") (name "unconnected-(U3B-NC_M10-PadM10)") (class "Default")
      (node (ref "U3") (pin "M10") (pinfunction "NC_M10_M10") (pintype "passive+no_connect"))
    )
    (net (code "143") (name "unconnected-(U3B-NC_M11-PadM11)") (class "Default")
      (node (ref "U3") (pin "M11") (pinfunction "NC_M11_M11") (pintype "passive+no_connect"))
    )
    (net (code "144") (name "unconnected-(U3B-NC_M12-PadM12)") (class "Default")
      (node (ref "U3") (pin "M12") (pinfunction "NC_M12_M12") (pintype "passive+no_connect"))
    )
    (net (code "145") (name "unconnected-(U3B-NC_M13-PadM13)") (class "Default")
      (node (ref "U3") (pin "M13") (pinfunction "NC_M13_M13") (pintype "passive+no_connect"))
    )
    (net (code "146") (name "unconnected-(U3B-NC_M14-PadM14)") (class "Default")
      (node (ref "U3") (pin "M14") (pinfunction "NC_M14_M14") (pintype "passive+no_connect"))
    )
    (net (code "147") (name "unconnected-(U3B-NC_N1-PadN1)") (class "Default")
      (node (ref "U3") (pin "N1") (pinfunction "NC_N1_N1") (pintype "passive+no_connect"))
    )
    (net (code "148") (name "unconnected-(U3B-NC_N3-PadN3)") (class "Default")
      (node (ref "U3") (pin "N3") (pinfunction "NC_N3_N3") (pintype "passive+no_connect"))
    )
    (net (code "149") (name "unconnected-(U3B-NC_N6-PadN6)") (class "Default")
      (node (ref "U3") (pin "N6") (pinfunction "NC_N6_N6") (pintype "passive+no_connect"))
    )
    (net (code "150") (name "unconnected-(U3B-NC_N7-PadN7)") (class "Default")
      (node (ref "U3") (pin "N7") (pinfunction "NC_N7_N7") (pintype "passive+no_connect"))
    )
    (net (code "151") (name "unconnected-(U3B-NC_N8-PadN8)") (class "Default")
      (node (ref "U3") (pin "N8") (pinfunction "NC_N8_N8") (pintype "passive+no_connect"))
    )
    (net (code "152") (name "unconnected-(U3B-NC_N9-PadN9)") (class "Default")
      (node (ref "U3") (pin "N9") (pinfunction "NC_N9_N9") (pintype "passive+no_connect"))
    )
    (net (code "153") (name "unconnected-(U3B-NC_N10-PadN10)") (class "Default")
      (node (ref "U3") (pin "N10") (pinfunction "NC_N10_N10") (pintype "passive+no_connect"))
    )
    (net (code "154") (name "unconnected-(U3B-NC_N11-PadN11)") (class "Default")
      (node (ref "U3") (pin "N11") (pinfunction "NC_N11_N11") (pintype "passive+no_connect"))
    )
    (net (code "155") (name "unconnected-(U3B-NC_N12-PadN12)") (class "Default")
      (node (ref "U3") (pin "N12") (pinfunction "NC_N12_N12") (pintype "passive+no_connect"))
    )
    (net (code "156") (name "unconnected-(U3B-NC_N13-PadN13)") (class "Default")
      (node (ref "U3") (pin "N13") (pinfunction "NC_N13_N13") (pintype "passive+no_connect"))
    )
    (net (code "157") (name "unconnected-(U3B-NC_N14-PadN14)") (class "Default")
      (node (ref "U3") (pin "N14") (pinfunction "NC_N14_N14") (pintype "passive+no_connect"))
    )
    (net (code "158") (name "unconnected-(U3B-NC_P1-PadP1)") (class "Default")
      (node (ref "U3") (pin "P1") (pinfunction "NC_P1_P1") (pintype "passive+no_connect"))
    )
    (net (code "159") (name "unconnected-(U3B-NC_P2-PadP2)") (class "Default")
      (node (ref "U3") (pin "P2") (pinfunction "NC_P2_P2") (pintype "passive+no_connect"))
    )
    (net (code "160") (name "unconnected-(U3B-NC_P7-PadP7)") (class "Default")
      (node (ref "U3") (pin "P7") (pinfunction "NC_P7_P7") (pintype "passive+no_connect"))
    )
    (net (code "161") (name "unconnected-(U3B-NC_P8-PadP8)") (class "Default")
      (node (ref "U3") (pin "P8") (pinfunction "NC_P8_P8") (pintype "passive+no_connect"))
    )
    (net (code "162") (name "unconnected-(U3B-NC_P9-PadP9)") (class "Default")
      (node (ref "U3") (pin "P9") (pinfunction "NC_P9_P9") (pintype "passive+no_connect"))
    )
    (net (code "163") (name "unconnected-(U3B-NC_P10-PadP10)") (class "Default")
      (node (ref "U3") (pin "P10") (pinfunction "NC_P10_P10") (pintype "passive+no_connect"))
    )
    (net (code "164") (name "unconnected-(U3B-NC_P11-PadP11)") (class "Default")
      (node (ref "U3") (pin "P11") (pinfunction "NC_P11_P11") (pintype "passive+no_connect"))
    )
    (net (code "165") (name "unconnected-(U3B-NC_P12-PadP12)") (class "Default")
      (node (ref "U3") (pin "P12") (pinfunction "NC_P12_P12") (pintype "passive+no_connect"))
    )
    (net (code "166") (name "unconnected-(U3B-NC_P13-PadP13)") (class "Default")
      (node (ref "U3") (pin "P13") (pinfunction "NC_P13_P13") (pintype "passive+no_connect"))
    )
    (net (code "167") (name "unconnected-(U3B-NC_P14-PadP14)") (class "Default")
      (node (ref "U3") (pin "P14") (pinfunction "NC_P14_P14") (pintype "passive+no_connect"))
    )
    (net (code "168") (name "unconnected-(U3B-VSF1-PadE9)") (class "Default")
      (node (ref "U3") (pin "E9") (pinfunction "VSF1_E9") (pintype "passive+no_connect"))
    )
    (net (code "169") (name "unconnected-(U3B-VSF2-PadE10)") (class "Default")
      (node (ref "U3") (pin "E10") (pinfunction "VSF2_E10") (pintype "passive+no_connect"))
    )
    (net (code "170") (name "unconnected-(U3B-VSF3-PadF10)") (class "Default")
      (node (ref "U3") (pin "F10") (pinfunction "VSF3_F10") (pintype "passive+no_connect"))
    )
    (net (code "171") (name "unconnected-(U3B-VSF4-PadK10)") (class "Default")
      (node (ref "U3") (pin "K10") (pinfunction "VSF4_K10") (pintype "passive+no_connect"))
    )
  )
)
